# recieving_end_copy-1.net
KiCad netlist of a schematic drawn in EAGLE
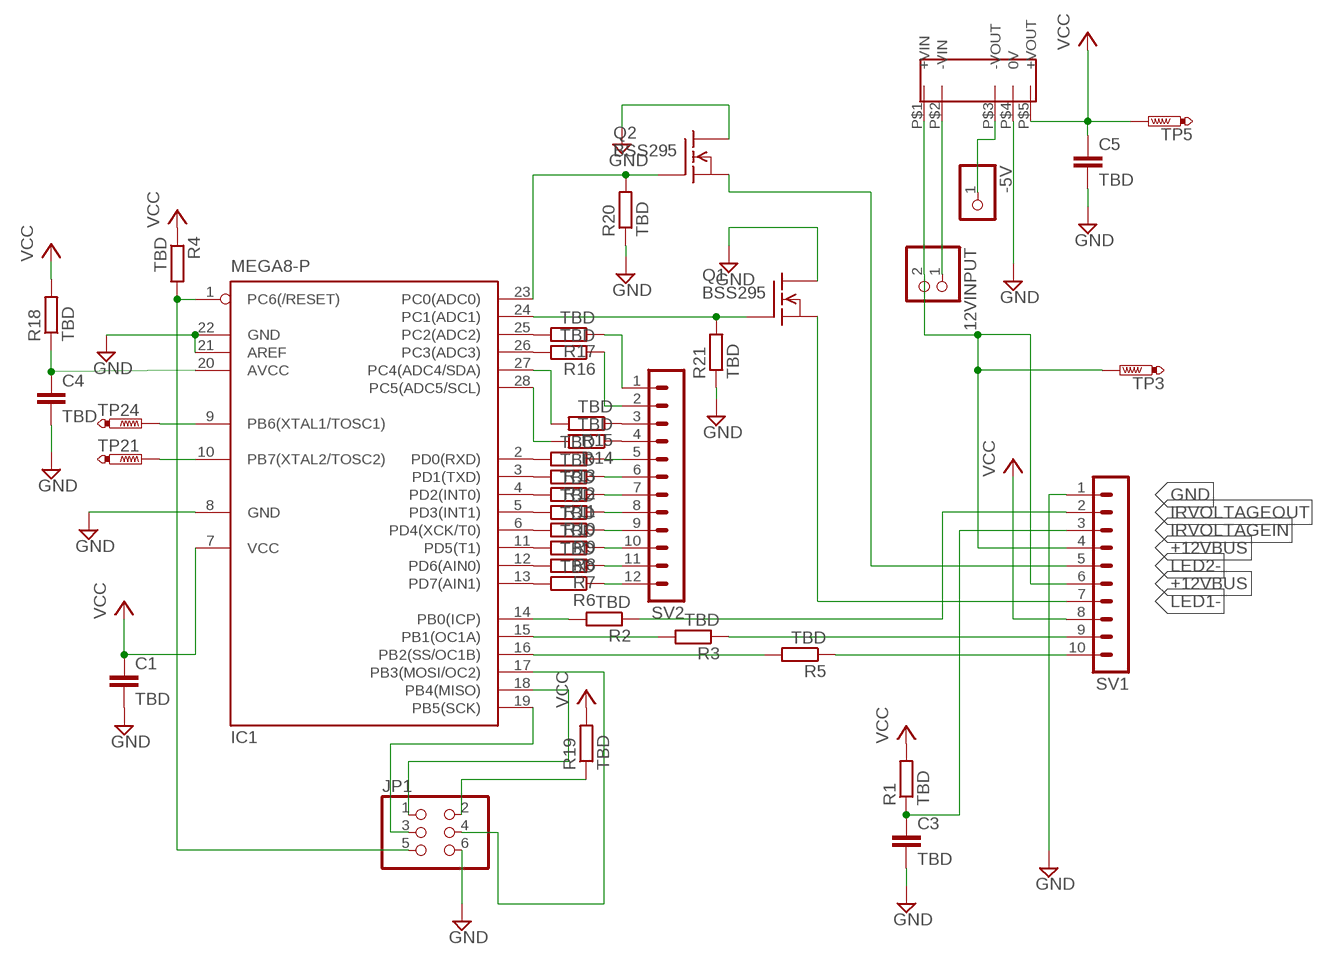
[diagram p0: schematic, sheet 1]

(export (version "E")
  (design (tool "Eeschema 10.0.6"))
  (components
    (comp (ref "-5V")
      (value "PINHD-1X1")
      (footprint "eagle-import:1X01")
      (libsource (lib "eagle-import") (part "PINHD-1X1"))
    )
    (comp (ref "12VINPUT")
      (value "PINHD-1X2")
      (footprint "eagle-import:1X02")
      (libsource (lib "eagle-import") (part "PINHD-1X2"))
    )
    (comp (ref "C1")
      (value "TBD")
      (footprint "eagle-import:C0805")
      (libsource (lib "eagle-import") (part "C-EUC0805"))
    )
    (comp (ref "C3")
      (value "TBD")
      (footprint "eagle-import:C0805")
      (libsource (lib "eagle-import") (part "C-EUC0805"))
    )
    (comp (ref "C4")
      (value "TBD")
      (footprint "eagle-import:C0805")
      (libsource (lib "eagle-import") (part "C-EUC0805"))
    )
    (comp (ref "C5")
      (value "TBD")
      (footprint "eagle-import:C0805")
      (libsource (lib "eagle-import") (part "C-EUC0805"))
    )
    (comp (ref "IC1")
      (value "MEGA8-P")
      (footprint "eagle-import:DIL28-3")
      (libsource (lib "eagle-import") (part "MEGA8-P"))
    )
    (comp (ref "JP1")
      (value "PINHD-2X3")
      (footprint "eagle-import:2X03")
      (libsource (lib "eagle-import") (part "PINHD-2X3"))
    )
    (comp (ref "Q1")
      (value "BSS295")
      (footprint "eagle-import:TO92")
      (libsource (lib "eagle-import") (part "BSS295"))
    )
    (comp (ref "Q2")
      (value "BSS295")
      (footprint "eagle-import:TO92")
      (libsource (lib "eagle-import") (part "BSS295"))
    )
    (comp (ref "R1")
      (value "TBD")
      (footprint "eagle-import:R0805")
      (libsource (lib "eagle-import") (part "R-EU_R0805"))
    )
    (comp (ref "R2")
      (value "TBD")
      (footprint "eagle-import:R0805")
      (libsource (lib "eagle-import") (part "R-EU_R0805"))
    )
    (comp (ref "R3")
      (value "TBD")
      (footprint "eagle-import:R0805")
      (libsource (lib "eagle-import") (part "R-EU_R0805"))
    )
    (comp (ref "R4")
      (value "TBD")
      (footprint "eagle-import:R0805")
      (libsource (lib "eagle-import") (part "R-EU_R0805"))
    )
    (comp (ref "R5")
      (value "TBD")
      (footprint "eagle-import:R0805")
      (libsource (lib "eagle-import") (part "R-EU_R0805"))
    )
    (comp (ref "R6")
      (value "TBD")
      (footprint "eagle-import:R0805")
      (libsource (lib "eagle-import") (part "R-EU_R0805"))
    )
    (comp (ref "R7")
      (value "TBD")
      (footprint "eagle-import:R0805")
      (libsource (lib "eagle-import") (part "R-EU_R0805"))
    )
    (comp (ref "R8")
      (value "TBD")
      (footprint "eagle-import:R0805")
      (libsource (lib "eagle-import") (part "R-EU_R0805"))
    )
    (comp (ref "R9")
      (value "TBD")
      (footprint "eagle-import:R0805")
      (libsource (lib "eagle-import") (part "R-EU_R0805"))
    )
    (comp (ref "R10")
      (value "TBD")
      (footprint "eagle-import:R0805")
      (libsource (lib "eagle-import") (part "R-EU_R0805"))
    )
    (comp (ref "R11")
      (value "TBD")
      (footprint "eagle-import:R0805")
      (libsource (lib "eagle-import") (part "R-EU_R0805"))
    )
    (comp (ref "R12")
      (value "TBD")
      (footprint "eagle-import:R0805")
      (libsource (lib "eagle-import") (part "R-EU_R0805"))
    )
    (comp (ref "R13")
      (value "TBD")
      (footprint "eagle-import:R0805")
      (libsource (lib "eagle-import") (part "R-EU_R0805"))
    )
    (comp (ref "R14")
      (value "TBD")
      (footprint "eagle-import:R0805")
      (libsource (lib "eagle-import") (part "R-EU_R0805"))
    )
    (comp (ref "R15")
      (value "TBD")
      (footprint "eagle-import:R0805")
      (libsource (lib "eagle-import") (part "R-EU_R0805"))
    )
    (comp (ref "R16")
      (value "TBD")
      (footprint "eagle-import:R0805")
      (libsource (lib "eagle-import") (part "R-EU_R0805"))
    )
    (comp (ref "R17")
      (value "TBD")
      (footprint "eagle-import:R0805")
      (libsource (lib "eagle-import") (part "R-EU_R0805"))
    )
    (comp (ref "R18")
      (value "TBD")
      (footprint "eagle-import:R0805")
      (libsource (lib "eagle-import") (part "R-EU_R0805"))
    )
    (comp (ref "R19")
      (value "TBD")
      (footprint "eagle-import:R0805")
      (libsource (lib "eagle-import") (part "R-EU_R0805"))
    )
    (comp (ref "R20")
      (value "TBD")
      (footprint "eagle-import:R0805")
      (libsource (lib "eagle-import") (part "R-EU_R0805"))
    )
    (comp (ref "R21")
      (value "TBD")
      (footprint "eagle-import:R0805")
      (libsource (lib "eagle-import") (part "R-EU_R0805"))
    )
    (comp (ref "SV1")
      (value "MA10-1")
      (footprint "eagle-import:MA10-1")
      (libsource (lib "eagle-import") (part "MA10-1"))
    )
    (comp (ref "SV2")
      (value "MA12-1")
      (footprint "eagle-import:MA12-1")
      (libsource (lib "eagle-import") (part "MA12-1"))
    )
    (comp (ref "TP3")
      (value "PTR1B1,27")
      (footprint "eagle-import:B1,27")
      (libsource (lib "eagle-import") (part "PTR1B1,27"))
    )
    (comp (ref "TP5")
      (value "PTR1B1,27")
      (footprint "eagle-import:B1,27")
      (libsource (lib "eagle-import") (part "PTR1B1,27"))
    )
    (comp (ref "TP21")
      (value "PTR1B1,27")
      (footprint "eagle-import:B1,27")
      (libsource (lib "eagle-import") (part "PTR1B1,27"))
    )
    (comp (ref "TP24")
      (value "PTR1B1,27")
      (footprint "eagle-import:B1,27")
      (libsource (lib "eagle-import") (part "PTR1B1,27"))
    )
    (comp (ref "U$1")
      (value "NKA1205SC")
      (footprint "eagle-import:NKA1205SC")
      (libsource (lib "eagle-import") (part "NKA1205SC"))
    )
  )
  (nets
    (net (code "1") (name "+12VBUS") (class "Default")
      (node (ref "12VINPUT") (pin "2") (pinfunction "2_2") (pintype "passive"))
      (node (ref "SV1") (pin "4") (pinfunction "4_4") (pintype "passive"))
      (node (ref "SV1") (pin "6") (pinfunction "6_6") (pintype "passive"))
      (node (ref "TP3") (pin "TP") (pinfunction "TP_TP") (pintype "input"))
      (node (ref "U$1") (pin "P$1") (pinfunction "+VIN_P$1") (pintype "bidirectional"))
    )
    (net (code "2") (name "GND") (class "Default")
      (node (ref "C1") (pin "2") (pinfunction "2_2") (pintype "passive"))
      (node (ref "C3") (pin "2") (pinfunction "2_2") (pintype "passive"))
      (node (ref "C4") (pin "2") (pinfunction "2_2") (pintype "passive"))
      (node (ref "C5") (pin "2") (pinfunction "2_2") (pintype "passive"))
      (node (ref "IC1") (pin "21") (pinfunction "AREF_21") (pintype "passive"))
      (node (ref "IC1") (pin "22") (pinfunction "GND_22") (pintype "power_in"))
      (node (ref "IC1") (pin "8") (pinfunction "GND_8") (pintype "power_in"))
      (node (ref "JP1") (pin "6") (pinfunction "6_6") (pintype "passive"))
      (node (ref "Q1") (pin "2") (pinfunction "D_2") (pintype "passive"))
      (node (ref "Q2") (pin "2") (pinfunction "D_2") (pintype "passive"))
      (node (ref "R20") (pin "1") (pinfunction "1_1") (pintype "passive"))
      (node (ref "R21") (pin "1") (pinfunction "1_1") (pintype "passive"))
      (node (ref "SV1") (pin "1") (pinfunction "1_1") (pintype "passive"))
      (node (ref "U$1") (pin "P$4") (pinfunction "0V_P$4") (pintype "bidirectional"))
    )
    (net (code "3") (name "IRVOLTAGEIN") (class "Default")
      (node (ref "C3") (pin "1") (pinfunction "1_1") (pintype "passive"))
      (node (ref "R1") (pin "1") (pinfunction "1_1") (pintype "passive"))
      (node (ref "SV1") (pin "3") (pinfunction "3_3") (pintype "passive"))
    )
    (net (code "4") (name "IRVOLTAGEOUT") (class "Default")
      (node (ref "R2") (pin "1") (pinfunction "1_1") (pintype "passive"))
      (node (ref "SV1") (pin "2") (pinfunction "2_2") (pintype "passive"))
    )
    (net (code "5") (name "LED1-") (class "Default")
      (node (ref "Q1") (pin "3") (pinfunction "S_3") (pintype "passive"))
      (node (ref "SV1") (pin "7") (pinfunction "7_7") (pintype "passive"))
    )
    (net (code "6") (name "LED2-") (class "Default")
      (node (ref "Q2") (pin "3") (pinfunction "S_3") (pintype "passive"))
      (node (ref "SV1") (pin "5") (pinfunction "5_5") (pintype "passive"))
    )
    (net (code "7") (name "Net-(IC1-AVCC)") (class "Default")
      (node (ref "C4") (pin "1") (pinfunction "1_1") (pintype "passive"))
      (node (ref "IC1") (pin "20") (pinfunction "AVCC_20") (pintype "power_in"))
      (node (ref "R18") (pin "1") (pinfunction "1_1") (pintype "passive"))
    )
    (net (code "8") (name "Net-(IC1-PB0(ICP))") (class "Default")
      (node (ref "IC1") (pin "14") (pinfunction "PB0(ICP)_14") (pintype "bidirectional"))
      (node (ref "R2") (pin "2") (pinfunction "2_2") (pintype "passive"))
    )
    (net (code "9") (name "Net-(IC1-PB1(OC1A))") (class "Default")
      (node (ref "IC1") (pin "15") (pinfunction "PB1(OC1A)_15") (pintype "bidirectional"))
      (node (ref "R3") (pin "2") (pinfunction "2_2") (pintype "passive"))
    )
    (net (code "10") (name "Net-(IC1-PB2(SS{slash}OC1B))") (class "Default")
      (node (ref "IC1") (pin "16") (pinfunction "PB2(SS/OC1B)_16") (pintype "bidirectional"))
      (node (ref "R5") (pin "2") (pinfunction "2_2") (pintype "passive"))
    )
    (net (code "11") (name "Net-(IC1-PB3(MOSI{slash}OC2))") (class "Default")
      (node (ref "IC1") (pin "17") (pinfunction "PB3(MOSI/OC2)_17") (pintype "bidirectional"))
      (node (ref "JP1") (pin "4") (pinfunction "4_4") (pintype "passive"))
    )
    (net (code "12") (name "Net-(IC1-PB4(MISO))") (class "Default")
      (node (ref "IC1") (pin "18") (pinfunction "PB4(MISO)_18") (pintype "bidirectional"))
      (node (ref "JP1") (pin "1") (pinfunction "1_1") (pintype "passive"))
    )
    (net (code "13") (name "Net-(IC1-PB5(SCK))") (class "Default")
      (node (ref "IC1") (pin "19") (pinfunction "PB5(SCK)_19") (pintype "bidirectional"))
      (node (ref "JP1") (pin "3") (pinfunction "3_3") (pintype "passive"))
    )
    (net (code "14") (name "Net-(IC1-PB6(XTAL1{slash}TOSC1))") (class "Default")
      (node (ref "IC1") (pin "9") (pinfunction "PB6(XTAL1/TOSC1)_9") (pintype "bidirectional"))
      (node (ref "TP24") (pin "TP") (pinfunction "TP_TP") (pintype "input"))
    )
    (net (code "15") (name "Net-(IC1-PB7(XTAL2{slash}TOSC2))") (class "Default")
      (node (ref "IC1") (pin "10") (pinfunction "PB7(XTAL2/TOSC2)_10") (pintype "bidirectional"))
      (node (ref "TP21") (pin "TP") (pinfunction "TP_TP") (pintype "input"))
    )
    (net (code "16") (name "Net-(IC1-PC0(ADC0))") (class "Default")
      (node (ref "IC1") (pin "23") (pinfunction "PC0(ADC0)_23") (pintype "bidirectional"))
      (node (ref "Q2") (pin "1") (pinfunction "G_1") (pintype "passive"))
      (node (ref "R20") (pin "2") (pinfunction "2_2") (pintype "passive"))
    )
    (net (code "17") (name "Net-(IC1-PC1(ADC1))") (class "Default")
      (node (ref "IC1") (pin "24") (pinfunction "PC1(ADC1)_24") (pintype "bidirectional"))
      (node (ref "Q1") (pin "1") (pinfunction "G_1") (pintype "passive"))
      (node (ref "R21") (pin "2") (pinfunction "2_2") (pintype "passive"))
    )
    (net (code "18") (name "Net-(IC1-PC2(ADC2))") (class "Default")
      (node (ref "IC1") (pin "25") (pinfunction "PC2(ADC2)_25") (pintype "bidirectional"))
      (node (ref "R17") (pin "2") (pinfunction "2_2") (pintype "passive"))
    )
    (net (code "19") (name "Net-(IC1-PC3(ADC3))") (class "Default")
      (node (ref "IC1") (pin "26") (pinfunction "PC3(ADC3)_26") (pintype "bidirectional"))
      (node (ref "R16") (pin "2") (pinfunction "2_2") (pintype "passive"))
    )
    (net (code "20") (name "Net-(IC1-PC4(ADC4{slash}SDA))") (class "Default")
      (node (ref "IC1") (pin "27") (pinfunction "PC4(ADC4/SDA)_27") (pintype "bidirectional"))
      (node (ref "R15") (pin "2") (pinfunction "2_2") (pintype "passive"))
    )
    (net (code "21") (name "Net-(IC1-PC5(ADC5{slash}SCL))") (class "Default")
      (node (ref "IC1") (pin "28") (pinfunction "PC5(ADC5/SCL)_28") (pintype "bidirectional"))
      (node (ref "R14") (pin "2") (pinfunction "2_2") (pintype "passive"))
    )
    (net (code "22") (name "Net-(IC1-PC6({slash}RESET))") (class "Default")
      (node (ref "IC1") (pin "1") (pinfunction "PC6(/RESET)_1") (pintype "bidirectional"))
      (node (ref "JP1") (pin "5") (pinfunction "5_5") (pintype "passive"))
      (node (ref "R4") (pin "2") (pinfunction "2_2") (pintype "passive"))
    )
    (net (code "23") (name "Net-(IC1-PD0(RXD))") (class "Default")
      (node (ref "IC1") (pin "2") (pinfunction "PD0(RXD)_2") (pintype "bidirectional"))
      (node (ref "R13") (pin "2") (pinfunction "2_2") (pintype "passive"))
    )
    (net (code "24") (name "Net-(IC1-PD1(TXD))") (class "Default")
      (node (ref "IC1") (pin "3") (pinfunction "PD1(TXD)_3") (pintype "bidirectional"))
      (node (ref "R12") (pin "2") (pinfunction "2_2") (pintype "passive"))
    )
    (net (code "25") (name "Net-(IC1-PD2(INT0))") (class "Default")
      (node (ref "IC1") (pin "4") (pinfunction "PD2(INT0)_4") (pintype "bidirectional"))
      (node (ref "R11") (pin "2") (pinfunction "2_2") (pintype "passive"))
    )
    (net (code "26") (name "Net-(IC1-PD3(INT1))") (class "Default")
      (node (ref "IC1") (pin "5") (pinfunction "PD3(INT1)_5") (pintype "bidirectional"))
      (node (ref "R10") (pin "2") (pinfunction "2_2") (pintype "passive"))
    )
    (net (code "27") (name "Net-(IC1-PD4(XCK{slash}T0))") (class "Default")
      (node (ref "IC1") (pin "6") (pinfunction "PD4(XCK/T0)_6") (pintype "bidirectional"))
      (node (ref "R9") (pin "2") (pinfunction "2_2") (pintype "passive"))
    )
    (net (code "28") (name "Net-(IC1-PD5(T1))") (class "Default")
      (node (ref "IC1") (pin "11") (pinfunction "PD5(T1)_11") (pintype "bidirectional"))
      (node (ref "R8") (pin "2") (pinfunction "2_2") (pintype "passive"))
    )
    (net (code "29") (name "Net-(IC1-PD6(AIN0))") (class "Default")
      (node (ref "IC1") (pin "12") (pinfunction "PD6(AIN0)_12") (pintype "bidirectional"))
      (node (ref "R7") (pin "2") (pinfunction "2_2") (pintype "passive"))
    )
    (net (code "30") (name "Net-(IC1-PD7(AIN1))") (class "Default")
      (node (ref "IC1") (pin "13") (pinfunction "PD7(AIN1)_13") (pintype "bidirectional"))
      (node (ref "R6") (pin "2") (pinfunction "2_2") (pintype "passive"))
    )
    (net (code "31") (name "Net-(JP1-Pad2)") (class "Default")
      (node (ref "JP1") (pin "2") (pinfunction "2_2") (pintype "passive"))
      (node (ref "R19") (pin "1") (pinfunction "1_1") (pintype "passive"))
    )
    (net (code "32") (name "Net-(R3-Pad1)") (class "Default")
      (node (ref "R3") (pin "1") (pinfunction "1_1") (pintype "passive"))
      (node (ref "SV1") (pin "9") (pinfunction "9_9") (pintype "passive"))
    )
    (net (code "33") (name "Net-(R5-Pad1)") (class "Default")
      (node (ref "R5") (pin "1") (pinfunction "1_1") (pintype "passive"))
      (node (ref "SV1") (pin "10") (pinfunction "10_10") (pintype "passive"))
    )
    (net (code "34") (name "Net-(R6-Pad1)") (class "Default")
      (node (ref "R6") (pin "1") (pinfunction "1_1") (pintype "passive"))
      (node (ref "SV2") (pin "12") (pinfunction "12_12") (pintype "passive"))
    )
    (net (code "35") (name "Net-(R7-Pad1)") (class "Default")
      (node (ref "R7") (pin "1") (pinfunction "1_1") (pintype "passive"))
      (node (ref "SV2") (pin "11") (pinfunction "11_11") (pintype "passive"))
    )
    (net (code "36") (name "Net-(R8-Pad1)") (class "Default")
      (node (ref "R8") (pin "1") (pinfunction "1_1") (pintype "passive"))
      (node (ref "SV2") (pin "10") (pinfunction "10_10") (pintype "passive"))
    )
    (net (code "37") (name "Net-(R9-Pad1)") (class "Default")
      (node (ref "R9") (pin "1") (pinfunction "1_1") (pintype "passive"))
      (node (ref "SV2") (pin "9") (pinfunction "9_9") (pintype "passive"))
    )
    (net (code "38") (name "Net-(R10-Pad1)") (class "Default")
      (node (ref "R10") (pin "1") (pinfunction "1_1") (pintype "passive"))
      (node (ref "SV2") (pin "8") (pinfunction "8_8") (pintype "passive"))
    )
    (net (code "39") (name "Net-(R11-Pad1)") (class "Default")
      (node (ref "R11") (pin "1") (pinfunction "1_1") (pintype "passive"))
      (node (ref "SV2") (pin "7") (pinfunction "7_7") (pintype "passive"))
    )
    (net (code "40") (name "Net-(R12-Pad1)") (class "Default")
      (node (ref "R12") (pin "1") (pinfunction "1_1") (pintype "passive"))
      (node (ref "SV2") (pin "6") (pinfunction "6_6") (pintype "passive"))
    )
    (net (code "41") (name "Net-(R13-Pad1)") (class "Default")
      (node (ref "R13") (pin "1") (pinfunction "1_1") (pintype "passive"))
      (node (ref "SV2") (pin "5") (pinfunction "5_5") (pintype "passive"))
    )
    (net (code "42") (name "Net-(R14-Pad1)") (class "Default")
      (node (ref "R14") (pin "1") (pinfunction "1_1") (pintype "passive"))
      (node (ref "SV2") (pin "4") (pinfunction "4_4") (pintype "passive"))
    )
    (net (code "43") (name "Net-(R15-Pad1)") (class "Default")
      (node (ref "R15") (pin "1") (pinfunction "1_1") (pintype "passive"))
      (node (ref "SV2") (pin "3") (pinfunction "3_3") (pintype "passive"))
    )
    (net (code "44") (name "Net-(R16-Pad1)") (class "Default")
      (node (ref "R16") (pin "1") (pinfunction "1_1") (pintype "passive"))
      (node (ref "SV2") (pin "2") (pinfunction "2_2") (pintype "passive"))
    )
    (net (code "45") (name "Net-(R17-Pad1)") (class "Default")
      (node (ref "R17") (pin "1") (pinfunction "1_1") (pintype "passive"))
      (node (ref "SV2") (pin "1") (pinfunction "1_1") (pintype "passive"))
    )
    (net (code "46") (name "Net-(U$1--VIN)") (class "Default")
      (node (ref "12VINPUT") (pin "1") (pinfunction "1_1") (pintype "passive"))
      (node (ref "U$1") (pin "P$2") (pinfunction "-VIN_P$2") (pintype "bidirectional"))
    )
    (net (code "47") (name "Net-(U$1--VOUT)") (class "Default")
      (node (ref "-5V") (pin "1") (pinfunction "1_1") (pintype "passive"))
      (node (ref "U$1") (pin "P$3") (pinfunction "-VOUT_P$3") (pintype "bidirectional"))
    )
    (net (code "48") (name "VCC") (class "Default")
      (node (ref "C1") (pin "1") (pinfunction "1_1") (pintype "passive"))
      (node (ref "C5") (pin "1") (pinfunction "1_1") (pintype "passive"))
      (node (ref "IC1") (pin "7") (pinfunction "VCC_7") (pintype "power_in"))
      (node (ref "R1") (pin "2") (pinfunction "2_2") (pintype "passive"))
      (node (ref "R18") (pin "2") (pinfunction "2_2") (pintype "passive"))
      (node (ref "R19") (pin "2") (pinfunction "2_2") (pintype "passive"))
      (node (ref "R4") (pin "1") (pinfunction "1_1") (pintype "passive"))
      (node (ref "SV1") (pin "8") (pinfunction "8_8") (pintype "passive"))
      (node (ref "TP5") (pin "TP") (pinfunction "TP_TP") (pintype "input"))
      (node (ref "U$1") (pin "P$5") (pinfunction "+VOUT_P$5") (pintype "bidirectional"))
    )
  )
)
